# UrLab_badge.net
KiCad netlist of a schematic drawn in EasyEDA
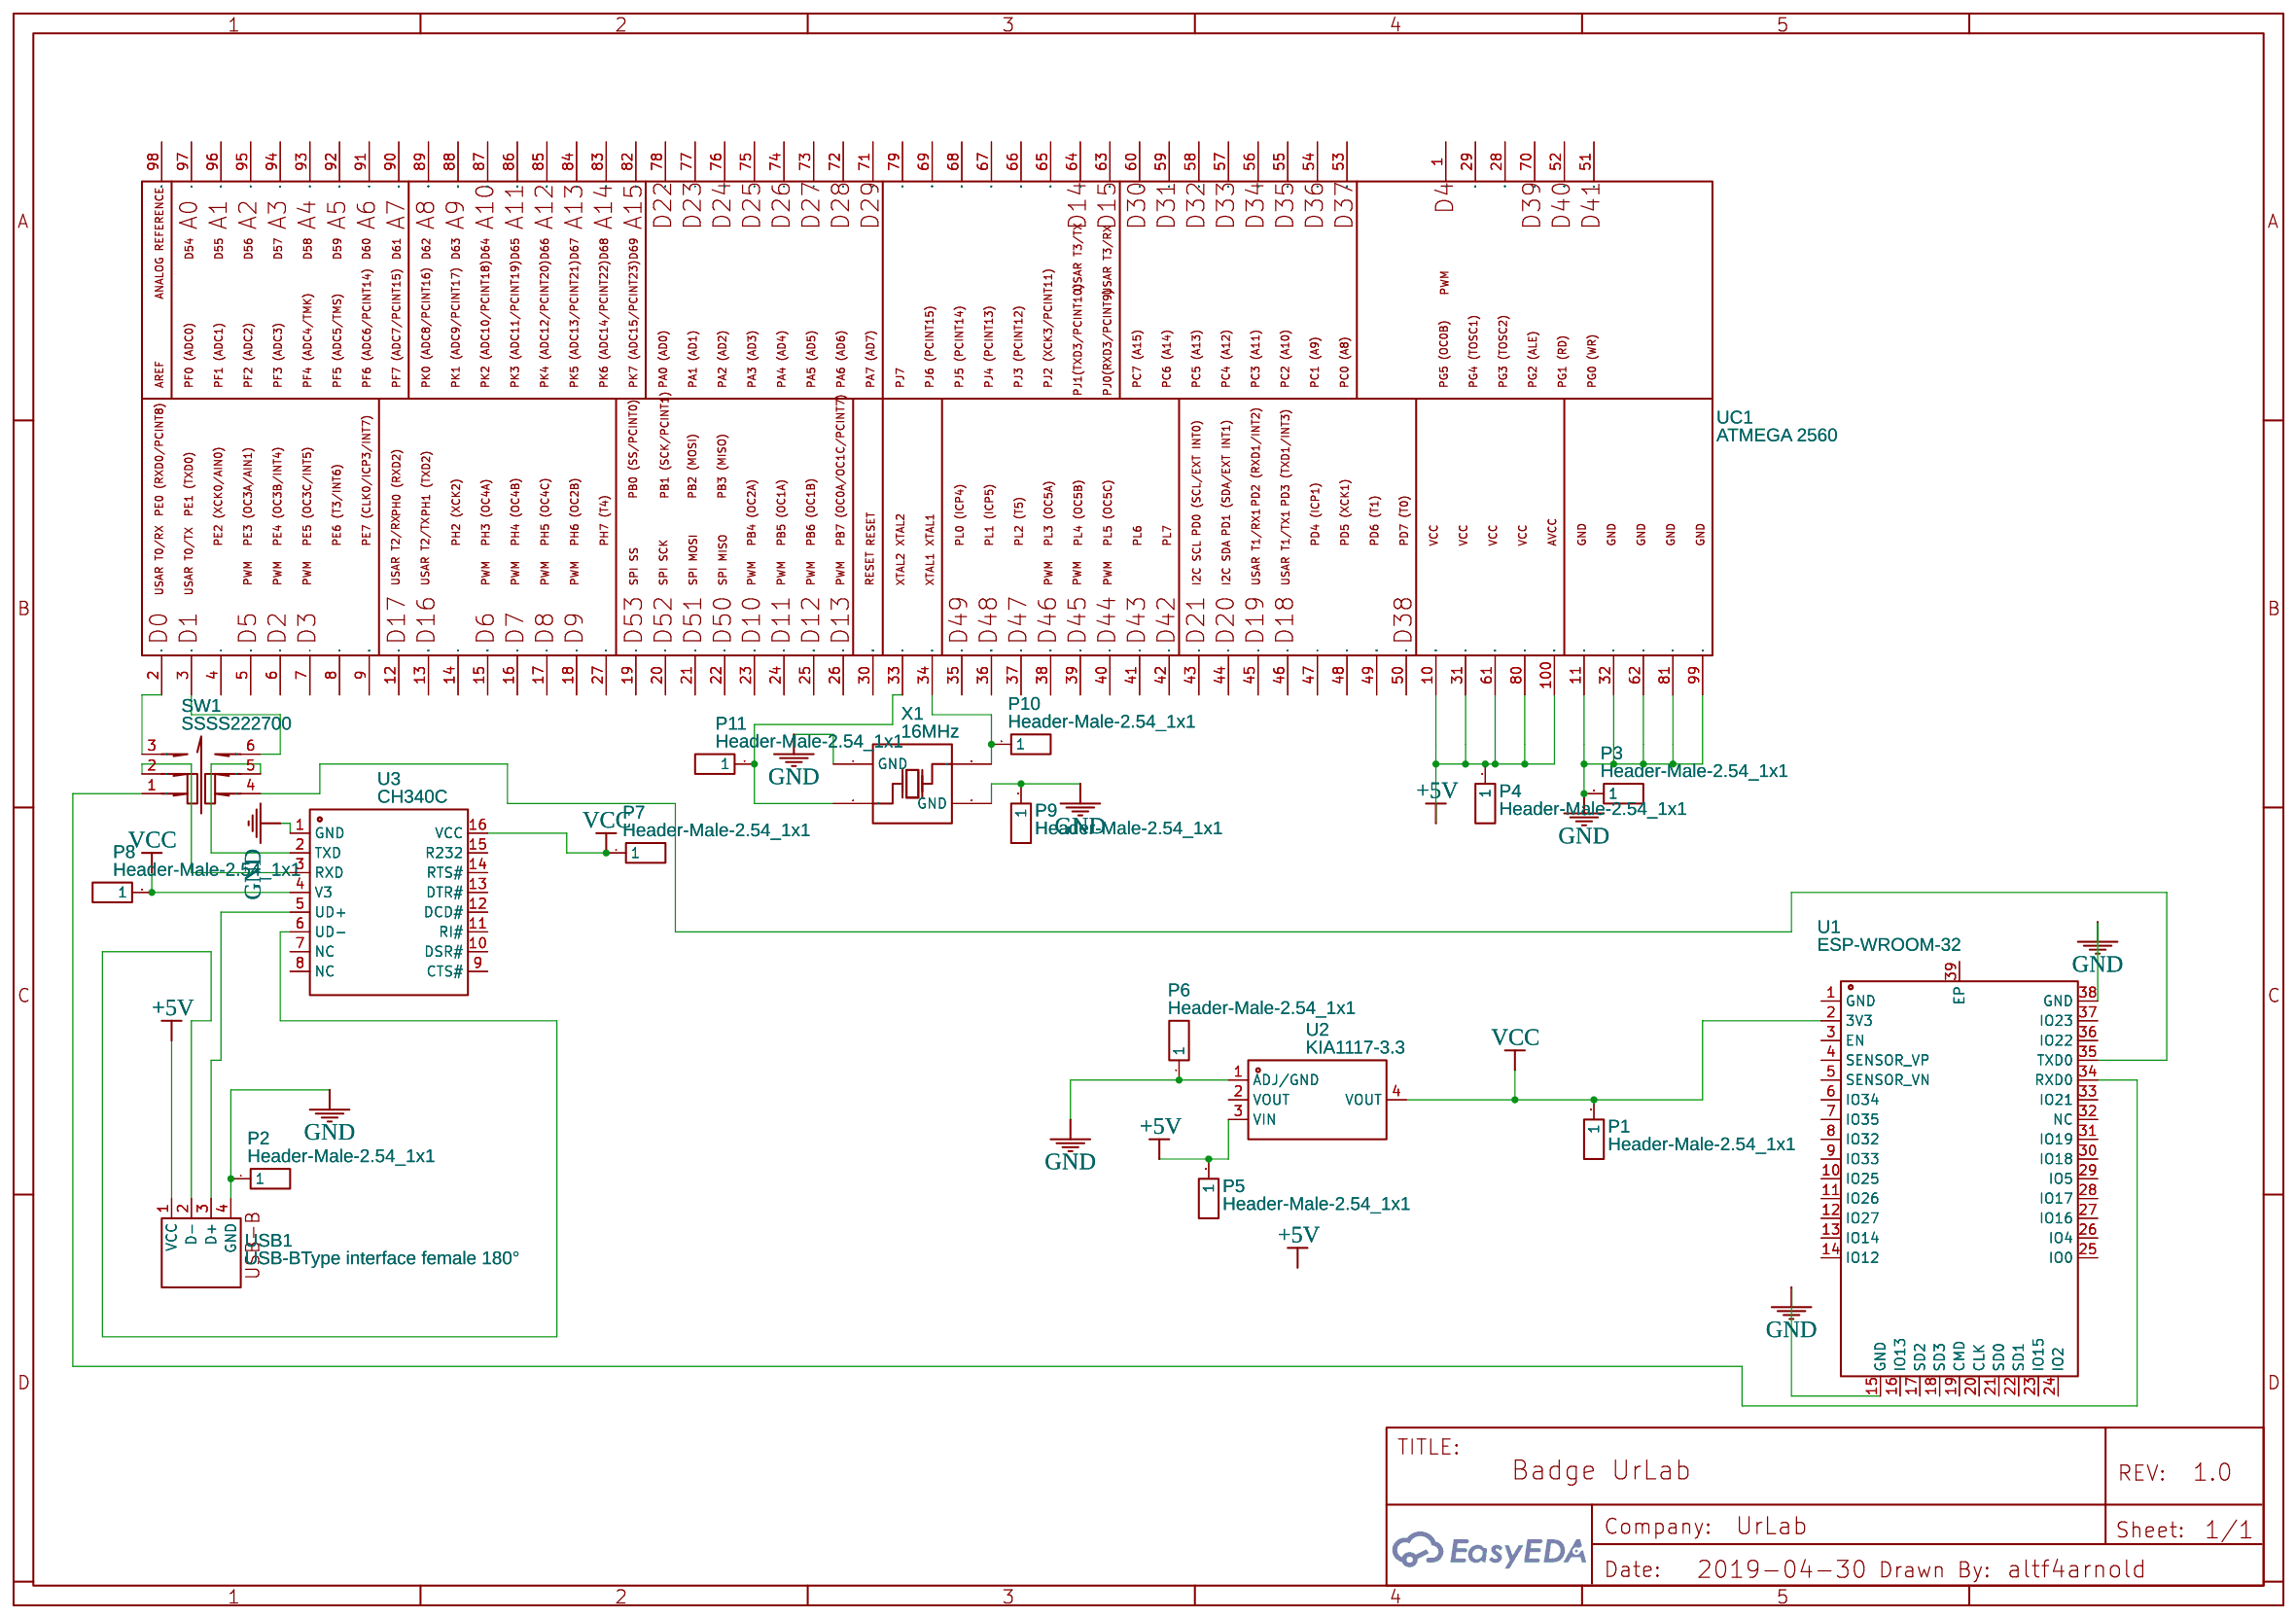
[diagram p0: schematic sheet]

(export (version "E")
  (design (tool "Eeschema 10.0.6"))
  (components
    (comp (ref "P1")
      (value "Header-Male-2.54_1x1")
      (fields (field (name "BOM_Supplier Part") "C81276"))
      (libsource (lib "") (part "Unknown_795_570"))
    )
    (comp (ref "P2")
      (value "Header-Male-2.54_1x1")
      (fields (field (name "BOM_Supplier Part") "C81276"))
      (libsource (lib "") (part "Unknown_120_595"))
    )
    (comp (ref "P3")
      (value "Header-Male-2.54_1x1")
      (fields (field (name "BOM_Supplier Part") "C81276"))
      (libsource (lib "") (part "Unknown_805_400"))
    )
    (comp (ref "P4")
      (value "Header-Male-2.54_1x1")
      (fields (field (name "BOM_Supplier Part") "C81276"))
      (libsource (lib "") (part "Unknown_740_400"))
    )
    (comp (ref "P5")
      (value "Header-Male-2.54_1x1")
      (fields (field (name "BOM_Supplier Part") "C81276"))
      (libsource (lib "") (part "Unknown_600_600"))
    )
    (comp (ref "P6")
      (value "Header-Male-2.54_1x1")
      (fields (field (name "BOM_Supplier Part") "C81276"))
      (libsource (lib "") (part "Unknown_585_530"))
    )
    (comp (ref "P7")
      (value "Header-Male-2.54_1x1")
      (fields (field (name "BOM_Supplier Part") "C81276"))
      (libsource (lib "") (part "Unknown_310_430"))
    )
    (comp (ref "P8")
      (value "Header-Male-2.54_1x1")
      (fields (field (name "BOM_Supplier Part") "C81276"))
      (libsource (lib "") (part "Unknown_50_450"))
    )
    (comp (ref "P9")
      (value "Header-Male-2.54_1x1")
      (fields (field (name "BOM_Supplier Part") "C81276"))
      (libsource (lib "") (part "Unknown_505_410"))
    )
    (comp (ref "P10")
      (value "Header-Male-2.54_1x1")
      (fields (field (name "BOM_Supplier Part") "C81276"))
      (libsource (lib "") (part "Unknown_505_375"))
    )
    (comp (ref "P11")
      (value "Header-Male-2.54_1x1")
      (fields (field (name "BOM_Supplier Part") "C81276"))
      (libsource (lib "") (part "Unknown_355_385"))
    )
    (comp (ref "SW1")
      (value "SSSS222700")
      (fields (field (name "BOM_Supplier Part") "C136144"))
      (libsource (lib "") (part "Unknown_90_390"))
    )
    (comp (ref "U1")
      (value "ESP-WROOM-32")
      (fields (field (name "BOM_Supplier Part") "C95209"))
      (libsource (lib "") (part "Unknown_980_600"))
    )
    (comp (ref "U2")
      (value "KIA1117-3.3")
      (fields (field (name "BOM_Supplier Part") "C116069"))
      (libsource (lib "") (part "Unknown_655_555"))
    )
    (comp (ref "U3")
      (value "CH340C")
      (fields (field (name "BOM_Supplier Part") "C84681"))
      (libsource (lib "") (part "Unknown_185_455"))
    )
    (comp (ref "UC1")
      (value "ATMEGA 2560")
      (fields (field (name "BOM_Manufacturer Part") "ATMEGA 2560 /1/1"))
      (libsource (lib "") (part "Unknown_450_210"))
    )
    (comp (ref "USB1")
      (value "USB-BType interface female 180°")
      (fields (field (name "BOM_Supplier Part") "C26234"))
      (libsource (lib "") (part "Unknown_90_630"))
    )
    (comp (ref "X1")
      (value "16MHz")
      (fields
        (field (name "BOM_Manufacturer Part") "Q24FA20H00530")
        (field (name "BOM_Supplier Part") "C255945")
      )
      (libsource (lib "") (part "Q24FA20H00530"))
    )
  )
  (nets
    (net (code "1") (name "+5V") (class "Default")
      (node (ref "P4") (pin "1") (pinfunction "1_1") (pintype "input"))
      (node (ref "P5") (pin "1") (pinfunction "1_1") (pintype "input"))
      (node (ref "U2") (pin "3") (pinfunction "VIN_3") (pintype "unspecified"))
      (node (ref "UC1") (pin "10") (pinfunction "10_10") (pintype "unspecified"))
      (node (ref "UC1") (pin "100") (pinfunction "100_100") (pintype "unspecified"))
      (node (ref "UC1") (pin "31") (pinfunction "31_31") (pintype "unspecified"))
      (node (ref "UC1") (pin "61") (pinfunction "61_61") (pintype "unspecified"))
      (node (ref "UC1") (pin "80") (pinfunction "80_80") (pintype "unspecified"))
      (node (ref "USB1") (pin "1") (pinfunction "VCC_1") (pintype "input"))
    )
    (net (code "2") (name "GND") (class "Default")
      (node (ref "P2") (pin "1") (pinfunction "1_1") (pintype "input"))
      (node (ref "P3") (pin "1") (pinfunction "1_1") (pintype "input"))
      (node (ref "P6") (pin "1") (pinfunction "1_1") (pintype "input"))
      (node (ref "P9") (pin "1") (pinfunction "1_1") (pintype "input"))
      (node (ref "U1") (pin "15") (pinfunction "GND_15") (pintype "unspecified"))
      (node (ref "U1") (pin "38") (pinfunction "GND_38") (pintype "unspecified"))
      (node (ref "U2") (pin "1") (pinfunction "ADJ/GND_1") (pintype "unspecified"))
      (node (ref "U3") (pin "1") (pinfunction "GND_1") (pintype "unspecified"))
      (node (ref "UC1") (pin "11") (pinfunction "11_11") (pintype "unspecified"))
      (node (ref "UC1") (pin "32") (pinfunction "32_32") (pintype "unspecified"))
      (node (ref "UC1") (pin "62") (pinfunction "62_62") (pintype "unspecified"))
      (node (ref "UC1") (pin "81") (pinfunction "81_81") (pintype "unspecified"))
      (node (ref "UC1") (pin "99") (pinfunction "99_99") (pintype "unspecified"))
      (node (ref "USB1") (pin "4") (pinfunction "GND_4") (pintype "input"))
      (node (ref "X1") (pin "2") (pinfunction "GND_2") (pintype "input"))
      (node (ref "X1") (pin "4") (pinfunction "GND_4") (pintype "input"))
    )
    (net (code "3") (name "Net-(SW1-Pad3)") (class "Default")
      (node (ref "SW1") (pin "3") (pinfunction "3_3") (pintype "unspecified"))
      (node (ref "UC1") (pin "2") (pinfunction "2_2") (pintype "unspecified"))
    )
    (net (code "4") (name "Net-(SW1-Pad6)") (class "Default")
      (node (ref "SW1") (pin "6") (pinfunction "6_6") (pintype "unspecified"))
      (node (ref "UC1") (pin "3") (pinfunction "3_3") (pintype "unspecified"))
    )
    (net (code "5") (name "Net-(U1-RXD0)") (class "Default")
      (node (ref "SW1") (pin "1") (pinfunction "1_1") (pintype "unspecified"))
      (node (ref "U1") (pin "34") (pinfunction "RXD0_34") (pintype "unspecified"))
    )
    (net (code "6") (name "Net-(U1-TXD0)") (class "Default")
      (node (ref "SW1") (pin "4") (pinfunction "4_4") (pintype "unspecified"))
      (node (ref "U1") (pin "35") (pinfunction "TXD0_35") (pintype "unspecified"))
    )
    (net (code "7") (name "Net-(U3-RXD)") (class "Default")
      (node (ref "SW1") (pin "2") (pinfunction "2_2") (pintype "unspecified"))
      (node (ref "U3") (pin "3") (pinfunction "RXD_3") (pintype "unspecified"))
    )
    (net (code "8") (name "Net-(U3-TXD)") (class "Default")
      (node (ref "SW1") (pin "5") (pinfunction "5_5") (pintype "unspecified"))
      (node (ref "U3") (pin "2") (pinfunction "TXD_2") (pintype "unspecified"))
    )
    (net (code "9") (name "Net-(U3-UD+)") (class "Default")
      (node (ref "U3") (pin "5") (pinfunction "UD+_5") (pintype "unspecified"))
      (node (ref "USB1") (pin "3") (pinfunction "D+_3") (pintype "input"))
    )
    (net (code "10") (name "Net-(U3-UD-)") (class "Default")
      (node (ref "U3") (pin "6") (pinfunction "UD-_6") (pintype "unspecified"))
      (node (ref "USB1") (pin "2") (pinfunction "D-_2") (pintype "input"))
    )
    (net (code "11") (name "Net-(X1-OSC1)") (class "Default")
      (node (ref "P11") (pin "1") (pinfunction "1_1") (pintype "input"))
      (node (ref "UC1") (pin "33") (pinfunction "33_33") (pintype "unspecified"))
      (node (ref "X1") (pin "1") (pinfunction "OSC1_1") (pintype "input"))
    )
    (net (code "12") (name "Net-(X1-OSC2)") (class "Default")
      (node (ref "P10") (pin "1") (pinfunction "1_1") (pintype "input"))
      (node (ref "UC1") (pin "34") (pinfunction "34_34") (pintype "unspecified"))
      (node (ref "X1") (pin "3") (pinfunction "OSC2_3") (pintype "input"))
    )
    (net (code "13") (name "VCC") (class "Default")
      (node (ref "P1") (pin "1") (pinfunction "1_1") (pintype "input"))
      (node (ref "P7") (pin "1") (pinfunction "1_1") (pintype "input"))
      (node (ref "P8") (pin "1") (pinfunction "1_1") (pintype "input"))
      (node (ref "U1") (pin "2") (pinfunction "3V3_2") (pintype "unspecified"))
      (node (ref "U2") (pin "4") (pinfunction "VOUT_4") (pintype "unspecified"))
      (node (ref "U3") (pin "16") (pinfunction "VCC_16") (pintype "unspecified"))
      (node (ref "U3") (pin "4") (pinfunction "V3_4") (pintype "unspecified"))
    )
    (net (code "14") (name "unconnected-(U1-CLK-Pad20)") (class "Default")
      (node (ref "U1") (pin "20") (pinfunction "CLK_20") (pintype "unspecified"))
    )
    (net (code "15") (name "unconnected-(U1-CMD-Pad19)") (class "Default")
      (node (ref "U1") (pin "19") (pinfunction "CMD_19") (pintype "unspecified"))
    )
    (net (code "16") (name "unconnected-(U1-EN-Pad3)") (class "Default")
      (node (ref "U1") (pin "3") (pinfunction "EN_3") (pintype "unspecified"))
    )
    (net (code "17") (name "unconnected-(U1-EP-Pad39)") (class "Default")
      (node (ref "U1") (pin "39") (pinfunction "EP_39") (pintype "unspecified"))
    )
    (net (code "18") (name "unconnected-(U1-GND-Pad1)") (class "Default")
      (node (ref "U1") (pin "1") (pinfunction "GND_1") (pintype "unspecified"))
    )
    (net (code "19") (name "unconnected-(U1-IO0-Pad25)") (class "Default")
      (node (ref "U1") (pin "25") (pinfunction "IO0_25") (pintype "unspecified"))
    )
    (net (code "20") (name "unconnected-(U1-IO2-Pad24)") (class "Default")
      (node (ref "U1") (pin "24") (pinfunction "IO2_24") (pintype "unspecified"))
    )
    (net (code "21") (name "unconnected-(U1-IO4-Pad26)") (class "Default")
      (node (ref "U1") (pin "26") (pinfunction "IO4_26") (pintype "unspecified"))
    )
    (net (code "22") (name "unconnected-(U1-IO5-Pad29)") (class "Default")
      (node (ref "U1") (pin "29") (pinfunction "IO5_29") (pintype "unspecified"))
    )
    (net (code "23") (name "unconnected-(U1-IO12-Pad14)") (class "Default")
      (node (ref "U1") (pin "14") (pinfunction "IO12_14") (pintype "unspecified"))
    )
    (net (code "24") (name "unconnected-(U1-IO13-Pad16)") (class "Default")
      (node (ref "U1") (pin "16") (pinfunction "IO13_16") (pintype "unspecified"))
    )
    (net (code "25") (name "unconnected-(U1-IO14-Pad13)") (class "Default")
      (node (ref "U1") (pin "13") (pinfunction "IO14_13") (pintype "unspecified"))
    )
    (net (code "26") (name "unconnected-(U1-IO15-Pad23)") (class "Default")
      (node (ref "U1") (pin "23") (pinfunction "IO15_23") (pintype "unspecified"))
    )
    (net (code "27") (name "unconnected-(U1-IO16-Pad27)") (class "Default")
      (node (ref "U1") (pin "27") (pinfunction "IO16_27") (pintype "unspecified"))
    )
    (net (code "28") (name "unconnected-(U1-IO17-Pad28)") (class "Default")
      (node (ref "U1") (pin "28") (pinfunction "IO17_28") (pintype "unspecified"))
    )
    (net (code "29") (name "unconnected-(U1-IO18-Pad30)") (class "Default")
      (node (ref "U1") (pin "30") (pinfunction "IO18_30") (pintype "unspecified"))
    )
    (net (code "30") (name "unconnected-(U1-IO19-Pad31)") (class "Default")
      (node (ref "U1") (pin "31") (pinfunction "IO19_31") (pintype "unspecified"))
    )
    (net (code "31") (name "unconnected-(U1-IO21-Pad33)") (class "Default")
      (node (ref "U1") (pin "33") (pinfunction "IO21_33") (pintype "unspecified"))
    )
    (net (code "32") (name "unconnected-(U1-IO22-Pad36)") (class "Default")
      (node (ref "U1") (pin "36") (pinfunction "IO22_36") (pintype "unspecified"))
    )
    (net (code "33") (name "unconnected-(U1-IO23-Pad37)") (class "Default")
      (node (ref "U1") (pin "37") (pinfunction "IO23_37") (pintype "unspecified"))
    )
    (net (code "34") (name "unconnected-(U1-IO25-Pad10)") (class "Default")
      (node (ref "U1") (pin "10") (pinfunction "IO25_10") (pintype "unspecified"))
    )
    (net (code "35") (name "unconnected-(U1-IO26-Pad11)") (class "Default")
      (node (ref "U1") (pin "11") (pinfunction "IO26_11") (pintype "unspecified"))
    )
    (net (code "36") (name "unconnected-(U1-IO27-Pad12)") (class "Default")
      (node (ref "U1") (pin "12") (pinfunction "IO27_12") (pintype "unspecified"))
    )
    (net (code "37") (name "unconnected-(U1-IO32-Pad8)") (class "Default")
      (node (ref "U1") (pin "8") (pinfunction "IO32_8") (pintype "unspecified"))
    )
    (net (code "38") (name "unconnected-(U1-IO33-Pad9)") (class "Default")
      (node (ref "U1") (pin "9") (pinfunction "IO33_9") (pintype "unspecified"))
    )
    (net (code "39") (name "unconnected-(U1-IO34-Pad6)") (class "Default")
      (node (ref "U1") (pin "6") (pinfunction "IO34_6") (pintype "unspecified"))
    )
    (net (code "40") (name "unconnected-(U1-IO35-Pad7)") (class "Default")
      (node (ref "U1") (pin "7") (pinfunction "IO35_7") (pintype "unspecified"))
    )
    (net (code "41") (name "unconnected-(U1-NC-Pad32)") (class "Default")
      (node (ref "U1") (pin "32") (pinfunction "NC_32") (pintype "unspecified"))
    )
    (net (code "42") (name "unconnected-(U1-SD0-Pad21)") (class "Default")
      (node (ref "U1") (pin "21") (pinfunction "SD0_21") (pintype "unspecified"))
    )
    (net (code "43") (name "unconnected-(U1-SD1-Pad22)") (class "Default")
      (node (ref "U1") (pin "22") (pinfunction "SD1_22") (pintype "unspecified"))
    )
    (net (code "44") (name "unconnected-(U1-SD2-Pad17)") (class "Default")
      (node (ref "U1") (pin "17") (pinfunction "SD2_17") (pintype "unspecified"))
    )
    (net (code "45") (name "unconnected-(U1-SD3-Pad18)") (class "Default")
      (node (ref "U1") (pin "18") (pinfunction "SD3_18") (pintype "unspecified"))
    )
    (net (code "46") (name "unconnected-(U1-SENSOR_VN-Pad5)") (class "Default")
      (node (ref "U1") (pin "5") (pinfunction "SENSOR_VN_5") (pintype "unspecified"))
    )
    (net (code "47") (name "unconnected-(U1-SENSOR_VP-Pad4)") (class "Default")
      (node (ref "U1") (pin "4") (pinfunction "SENSOR_VP_4") (pintype "unspecified"))
    )
    (net (code "48") (name "unconnected-(U2-VOUT-Pad2)") (class "Default")
      (node (ref "U2") (pin "2") (pinfunction "VOUT_2") (pintype "unspecified"))
    )
    (net (code "49") (name "unconnected-(U3-CTS#-Pad9)") (class "Default")
      (node (ref "U3") (pin "9") (pinfunction "CTS#_9") (pintype "unspecified"))
    )
    (net (code "50") (name "unconnected-(U3-DCD#-Pad12)") (class "Default")
      (node (ref "U3") (pin "12") (pinfunction "DCD#_12") (pintype "unspecified"))
    )
    (net (code "51") (name "unconnected-(U3-DSR#-Pad10)") (class "Default")
      (node (ref "U3") (pin "10") (pinfunction "DSR#_10") (pintype "unspecified"))
    )
    (net (code "52") (name "unconnected-(U3-DTR#-Pad13)") (class "Default")
      (node (ref "U3") (pin "13") (pinfunction "DTR#_13") (pintype "unspecified"))
    )
    (net (code "53") (name "unconnected-(U3-NC-Pad7)") (class "Default")
      (node (ref "U3") (pin "7") (pinfunction "NC_7") (pintype "unspecified"))
    )
    (net (code "54") (name "unconnected-(U3-NC-Pad8)") (class "Default")
      (node (ref "U3") (pin "8") (pinfunction "NC_8") (pintype "unspecified"))
    )
    (net (code "55") (name "unconnected-(U3-R232-Pad15)") (class "Default")
      (node (ref "U3") (pin "15") (pinfunction "R232_15") (pintype "unspecified"))
    )
    (net (code "56") (name "unconnected-(U3-RI#-Pad11)") (class "Default")
      (node (ref "U3") (pin "11") (pinfunction "RI#_11") (pintype "unspecified"))
    )
    (net (code "57") (name "unconnected-(U3-RTS#-Pad14)") (class "Default")
      (node (ref "U3") (pin "14") (pinfunction "RTS#_14") (pintype "unspecified"))
    )
    (net (code "58") (name "unconnected-(UC1-Pad1)") (class "Default")
      (node (ref "UC1") (pin "1") (pinfunction "1_1") (pintype "unspecified"))
    )
    (net (code "59") (name "unconnected-(UC1-Pad4)") (class "Default")
      (node (ref "UC1") (pin "4") (pinfunction "4_4") (pintype "unspecified"))
    )
    (net (code "60") (name "unconnected-(UC1-Pad5)") (class "Default")
      (node (ref "UC1") (pin "5") (pinfunction "5_5") (pintype "unspecified"))
    )
    (net (code "61") (name "unconnected-(UC1-Pad6)") (class "Default")
      (node (ref "UC1") (pin "6") (pinfunction "6_6") (pintype "unspecified"))
    )
    (net (code "62") (name "unconnected-(UC1-Pad7)") (class "Default")
      (node (ref "UC1") (pin "7") (pinfunction "7_7") (pintype "unspecified"))
    )
    (net (code "63") (name "unconnected-(UC1-Pad8)") (class "Default")
      (node (ref "UC1") (pin "8") (pinfunction "8_8") (pintype "unspecified"))
    )
    (net (code "64") (name "unconnected-(UC1-Pad9)") (class "Default")
      (node (ref "UC1") (pin "9") (pinfunction "9_9") (pintype "unspecified"))
    )
    (net (code "65") (name "unconnected-(UC1-Pad12)") (class "Default")
      (node (ref "UC1") (pin "12") (pinfunction "12_12") (pintype "unspecified"))
    )
    (net (code "66") (name "unconnected-(UC1-Pad13)") (class "Default")
      (node (ref "UC1") (pin "13") (pinfunction "13_13") (pintype "unspecified"))
    )
    (net (code "67") (name "unconnected-(UC1-Pad14)") (class "Default")
      (node (ref "UC1") (pin "14") (pinfunction "14_14") (pintype "unspecified"))
    )
    (net (code "68") (name "unconnected-(UC1-Pad15)") (class "Default")
      (node (ref "UC1") (pin "15") (pinfunction "15_15") (pintype "unspecified"))
    )
    (net (code "69") (name "unconnected-(UC1-Pad16)") (class "Default")
      (node (ref "UC1") (pin "16") (pinfunction "16_16") (pintype "unspecified"))
    )
    (net (code "70") (name "unconnected-(UC1-Pad17)") (class "Default")
      (node (ref "UC1") (pin "17") (pinfunction "17_17") (pintype "unspecified"))
    )
    (net (code "71") (name "unconnected-(UC1-Pad18)") (class "Default")
      (node (ref "UC1") (pin "18") (pinfunction "18_18") (pintype "unspecified"))
    )
    (net (code "72") (name "unconnected-(UC1-Pad19)") (class "Default")
      (node (ref "UC1") (pin "19") (pinfunction "19_19") (pintype "unspecified"))
    )
    (net (code "73") (name "unconnected-(UC1-Pad20)") (class "Default")
      (node (ref "UC1") (pin "20") (pinfunction "20_20") (pintype "unspecified"))
    )
    (net (code "74") (name "unconnected-(UC1-Pad21)") (class "Default")
      (node (ref "UC1") (pin "21") (pinfunction "21_21") (pintype "unspecified"))
    )
    (net (code "75") (name "unconnected-(UC1-Pad22)") (class "Default")
      (node (ref "UC1") (pin "22") (pinfunction "22_22") (pintype "unspecified"))
    )
    (net (code "76") (name "unconnected-(UC1-Pad23)") (class "Default")
      (node (ref "UC1") (pin "23") (pinfunction "23_23") (pintype "unspecified"))
    )
    (net (code "77") (name "unconnected-(UC1-Pad24)") (class "Default")
      (node (ref "UC1") (pin "24") (pinfunction "24_24") (pintype "unspecified"))
    )
    (net (code "78") (name "unconnected-(UC1-Pad25)") (class "Default")
      (node (ref "UC1") (pin "25") (pinfunction "25_25") (pintype "unspecified"))
    )
    (net (code "79") (name "unconnected-(UC1-Pad26)") (class "Default")
      (node (ref "UC1") (pin "26") (pinfunction "26_26") (pintype "unspecified"))
    )
    (net (code "80") (name "unconnected-(UC1-Pad27)") (class "Default")
      (node (ref "UC1") (pin "27") (pinfunction "27_27") (pintype "unspecified"))
    )
    (net (code "81") (name "unconnected-(UC1-Pad28)") (class "Default")
      (node (ref "UC1") (pin "28") (pinfunction "28_28") (pintype "unspecified"))
    )
    (net (code "82") (name "unconnected-(UC1-Pad29)") (class "Default")
      (node (ref "UC1") (pin "29") (pinfunction "29_29") (pintype "unspecified"))
    )
    (net (code "83") (name "unconnected-(UC1-Pad30)") (class "Default")
      (node (ref "UC1") (pin "30") (pinfunction "30_30") (pintype "unspecified"))
    )
    (net (code "84") (name "unconnected-(UC1-Pad35)") (class "Default")
      (node (ref "UC1") (pin "35") (pinfunction "35_35") (pintype "unspecified"))
    )
    (net (code "85") (name "unconnected-(UC1-Pad36)") (class "Default")
      (node (ref "UC1") (pin "36") (pinfunction "36_36") (pintype "unspecified"))
    )
    (net (code "86") (name "unconnected-(UC1-Pad37)") (class "Default")
      (node (ref "UC1") (pin "37") (pinfunction "37_37") (pintype "unspecified"))
    )
    (net (code "87") (name "unconnected-(UC1-Pad38)") (class "Default")
      (node (ref "UC1") (pin "38") (pinfunction "38_38") (pintype "unspecified"))
    )
    (net (code "88") (name "unconnected-(UC1-Pad39)") (class "Default")
      (node (ref "UC1") (pin "39") (pinfunction "39_39") (pintype "unspecified"))
    )
    (net (code "89") (name "unconnected-(UC1-Pad40)") (class "Default")
      (node (ref "UC1") (pin "40") (pinfunction "40_40") (pintype "unspecified"))
    )
    (net (code "90") (name "unconnected-(UC1-Pad41)") (class "Default")
      (node (ref "UC1") (pin "41") (pinfunction "41_41") (pintype "unspecified"))
    )
    (net (code "91") (name "unconnected-(UC1-Pad42)") (class "Default")
      (node (ref "UC1") (pin "42") (pinfunction "42_42") (pintype "unspecified"))
    )
    (net (code "92") (name "unconnected-(UC1-Pad43)") (class "Default")
      (node (ref "UC1") (pin "43") (pinfunction "43_43") (pintype "unspecified"))
    )
    (net (code "93") (name "unconnected-(UC1-Pad44)") (class "Default")
      (node (ref "UC1") (pin "44") (pinfunction "44_44") (pintype "unspecified"))
    )
    (net (code "94") (name "unconnected-(UC1-Pad45)") (class "Default")
      (node (ref "UC1") (pin "45") (pinfunction "45_45") (pintype "unspecified"))
    )
    (net (code "95") (name "unconnected-(UC1-Pad46)") (class "Default")
      (node (ref "UC1") (pin "46") (pinfunction "46_46") (pintype "unspecified"))
    )
    (net (code "96") (name "unconnected-(UC1-Pad47)") (class "Default")
      (node (ref "UC1") (pin "47") (pinfunction "47_47") (pintype "unspecified"))
    )
    (net (code "97") (name "unconnected-(UC1-Pad48)") (class "Default")
      (node (ref "UC1") (pin "48") (pinfunction "48_48") (pintype "unspecified"))
    )
    (net (code "98") (name "unconnected-(UC1-Pad49)") (class "Default")
      (node (ref "UC1") (pin "49") (pinfunction "49_49") (pintype "unspecified"))
    )
    (net (code "99") (name "unconnected-(UC1-Pad50)") (class "Default")
      (node (ref "UC1") (pin "50") (pinfunction "50_50") (pintype "unspecified"))
    )
    (net (code "100") (name "unconnected-(UC1-Pad51)") (class "Default")
      (node (ref "UC1") (pin "51") (pinfunction "51_51") (pintype "unspecified"))
    )
    (net (code "101") (name "unconnected-(UC1-Pad52)") (class "Default")
      (node (ref "UC1") (pin "52") (pinfunction "52_52") (pintype "unspecified"))
    )
    (net (code "102") (name "unconnected-(UC1-Pad53)") (class "Default")
      (node (ref "UC1") (pin "53") (pinfunction "53_53") (pintype "unspecified"))
    )
    (net (code "103") (name "unconnected-(UC1-Pad54)") (class "Default")
      (node (ref "UC1") (pin "54") (pinfunction "54_54") (pintype "unspecified"))
    )
    (net (code "104") (name "unconnected-(UC1-Pad55)") (class "Default")
      (node (ref "UC1") (pin "55") (pinfunction "55_55") (pintype "unspecified"))
    )
    (net (code "105") (name "unconnected-(UC1-Pad56)") (class "Default")
      (node (ref "UC1") (pin "56") (pinfunction "56_56") (pintype "unspecified"))
    )
    (net (code "106") (name "unconnected-(UC1-Pad57)") (class "Default")
      (node (ref "UC1") (pin "57") (pinfunction "57_57") (pintype "unspecified"))
    )
    (net (code "107") (name "unconnected-(UC1-Pad58)") (class "Default")
      (node (ref "UC1") (pin "58") (pinfunction "58_58") (pintype "unspecified"))
    )
    (net (code "108") (name "unconnected-(UC1-Pad59)") (class "Default")
      (node (ref "UC1") (pin "59") (pinfunction "59_59") (pintype "unspecified"))
    )
    (net (code "109") (name "unconnected-(UC1-Pad60)") (class "Default")
      (node (ref "UC1") (pin "60") (pinfunction "60_60") (pintype "unspecified"))
    )
    (net (code "110") (name "unconnected-(UC1-Pad63)") (class "Default")
      (node (ref "UC1") (pin "63") (pinfunction "63_63") (pintype "unspecified"))
    )
    (net (code "111") (name "unconnected-(UC1-Pad64)") (class "Default")
      (node (ref "UC1") (pin "64") (pinfunction "64_64") (pintype "unspecified"))
    )
    (net (code "112") (name "unconnected-(UC1-Pad65)") (class "Default")
      (node (ref "UC1") (pin "65") (pinfunction "65_65") (pintype "unspecified"))
    )
    (net (code "113") (name "unconnected-(UC1-Pad66)") (class "Default")
      (node (ref "UC1") (pin "66") (pinfunction "66_66") (pintype "unspecified"))
    )
    (net (code "114") (name "unconnected-(UC1-Pad67)") (class "Default")
      (node (ref "UC1") (pin "67") (pinfunction "67_67") (pintype "unspecified"))
    )
    (net (code "115") (name "unconnected-(UC1-Pad68)") (class "Default")
      (node (ref "UC1") (pin "68") (pinfunction "68_68") (pintype "unspecified"))
    )
    (net (code "116") (name "unconnected-(UC1-Pad69)") (class "Default")
      (node (ref "UC1") (pin "69") (pinfunction "69_69") (pintype "unspecified"))
    )
    (net (code "117") (name "unconnected-(UC1-Pad70)") (class "Default")
      (node (ref "UC1") (pin "70") (pinfunction "70_70") (pintype "unspecified"))
    )
    (net (code "118") (name "unconnected-(UC1-Pad71)") (class "Default")
      (node (ref "UC1") (pin "71") (pinfunction "71_71") (pintype "unspecified"))
    )
    (net (code "119") (name "unconnected-(UC1-Pad72)") (class "Default")
      (node (ref "UC1") (pin "72") (pinfunction "72_72") (pintype "unspecified"))
    )
    (net (code "120") (name "unconnected-(UC1-Pad73)") (class "Default")
      (node (ref "UC1") (pin "73") (pinfunction "73_73") (pintype "unspecified"))
    )
    (net (code "121") (name "unconnected-(UC1-Pad74)") (class "Default")
      (node (ref "UC1") (pin "74") (pinfunction "74_74") (pintype "unspecified"))
    )
    (net (code "122") (name "unconnected-(UC1-Pad75)") (class "Default")
      (node (ref "UC1") (pin "75") (pinfunction "75_75") (pintype "unspecified"))
    )
    (net (code "123") (name "unconnected-(UC1-Pad76)") (class "Default")
      (node (ref "UC1") (pin "76") (pinfunction "76_76") (pintype "unspecified"))
    )
    (net (code "124") (name "unconnected-(UC1-Pad77)") (class "Default")
      (node (ref "UC1") (pin "77") (pinfunction "77_77") (pintype "unspecified"))
    )
    (net (code "125") (name "unconnected-(UC1-Pad78)") (class "Default")
      (node (ref "UC1") (pin "78") (pinfunction "78_78") (pintype "unspecified"))
    )
    (net (code "126") (name "unconnected-(UC1-Pad79)") (class "Default")
      (node (ref "UC1") (pin "79") (pinfunction "79_79") (pintype "unspecified"))
    )
    (net (code "127") (name "unconnected-(UC1-Pad82)") (class "Default")
      (node (ref "UC1") (pin "82") (pinfunction "82_82") (pintype "unspecified"))
    )
    (net (code "128") (name "unconnected-(UC1-Pad83)") (class "Default")
      (node (ref "UC1") (pin "83") (pinfunction "83_83") (pintype "unspecified"))
    )
    (net (code "129") (name "unconnected-(UC1-Pad84)") (class "Default")
      (node (ref "UC1") (pin "84") (pinfunction "84_84") (pintype "unspecified"))
    )
    (net (code "130") (name "unconnected-(UC1-Pad85)") (class "Default")
      (node (ref "UC1") (pin "85") (pinfunction "85_85") (pintype "unspecified"))
    )
    (net (code "131") (name "unconnected-(UC1-Pad86)") (class "Default")
      (node (ref "UC1") (pin "86") (pinfunction "86_86") (pintype "unspecified"))
    )
    (net (code "132") (name "unconnected-(UC1-Pad87)") (class "Default")
      (node (ref "UC1") (pin "87") (pinfunction "87_87") (pintype "unspecified"))
    )
    (net (code "133") (name "unconnected-(UC1-Pad88)") (class "Default")
      (node (ref "UC1") (pin "88") (pinfunction "88_88") (pintype "unspecified"))
    )
    (net (code "134") (name "unconnected-(UC1-Pad89)") (class "Default")
      (node (ref "UC1") (pin "89") (pinfunction "89_89") (pintype "unspecified"))
    )
    (net (code "135") (name "unconnected-(UC1-Pad90)") (class "Default")
      (node (ref "UC1") (pin "90") (pinfunction "90_90") (pintype "unspecified"))
    )
    (net (code "136") (name "unconnected-(UC1-Pad91)") (class "Default")
      (node (ref "UC1") (pin "91") (pinfunction "91_91") (pintype "unspecified"))
    )
    (net (code "137") (name "unconnected-(UC1-Pad92)") (class "Default")
      (node (ref "UC1") (pin "92") (pinfunction "92_92") (pintype "unspecified"))
    )
    (net (code "138") (name "unconnected-(UC1-Pad93)") (class "Default")
      (node (ref "UC1") (pin "93") (pinfunction "93_93") (pintype "unspecified"))
    )
    (net (code "139") (name "unconnected-(UC1-Pad94)") (class "Default")
      (node (ref "UC1") (pin "94") (pinfunction "94_94") (pintype "unspecified"))
    )
    (net (code "140") (name "unconnected-(UC1-Pad95)") (class "Default")
      (node (ref "UC1") (pin "95") (pinfunction "95_95") (pintype "unspecified"))
    )
    (net (code "141") (name "unconnected-(UC1-Pad96)") (class "Default")
      (node (ref "UC1") (pin "96") (pinfunction "96_96") (pintype "unspecified"))
    )
    (net (code "142") (name "unconnected-(UC1-Pad97)") (class "Default")
      (node (ref "UC1") (pin "97") (pinfunction "97_97") (pintype "unspecified"))
    )
    (net (code "143") (name "unconnected-(UC1-Pad98)") (class "Default")
      (node (ref "UC1") (pin "98") (pinfunction "98_98") (pintype "unspecified"))
    )
  )
)
